# relay_matrix.net
KiCad netlist of a schematic drawn in Altium Designer
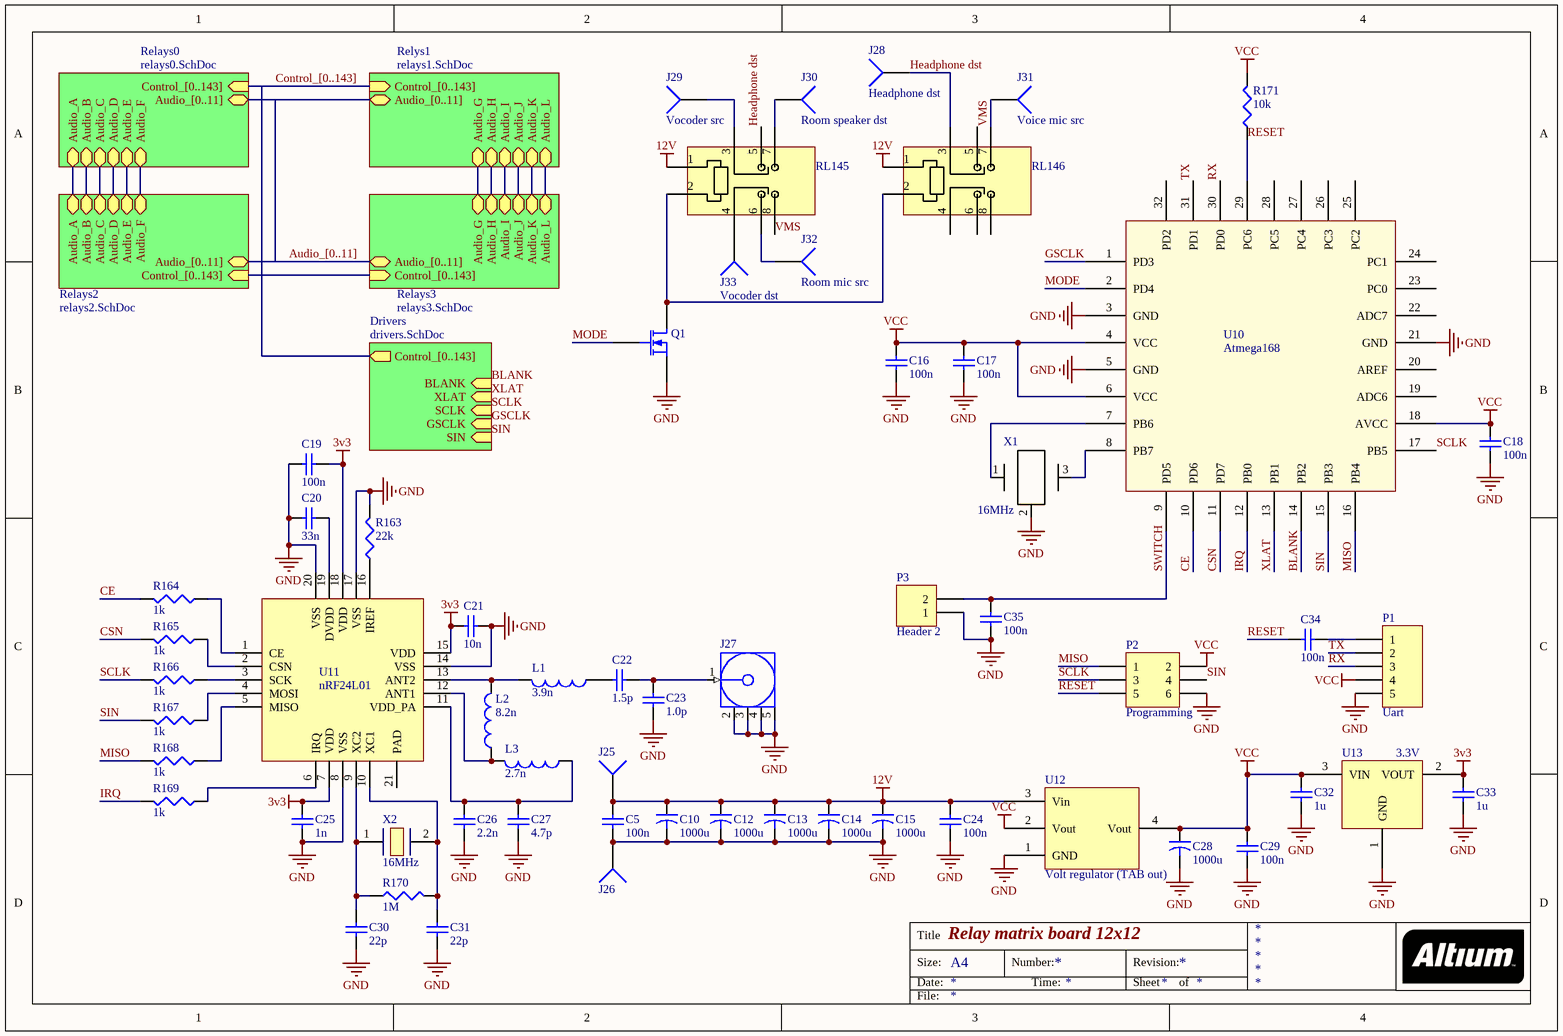
[diagram p0: relay_matrix.SchDoc]

(export (version "E")
  (design (tool "Eeschema 10.0.6"))
  (components
    (comp (ref "C5")
      (value "100n")
      (footprint "1608[0603]")
      (description "Capacitor (Semiconductor SIM Model)")
      (fields (field (name "Comment") "Cap Semi") (field (name "PUBLISHER") "Altium Limited"))
      (libsource (lib "Miscellaneous Devices") (part "Cap Semi"))
    )
    (comp (ref "C10")
      (value "1000u")
      (footprint "Cap_10x16mm")
      (description "Capacitor")
      (fields (field (name "Comment") "Cap2") (field (name "PUBLISHER") "Altium Limited"))
      (libsource (lib "Miscellaneous Devices") (part "Cap2"))
    )
    (comp (ref "C12")
      (value "1000u")
      (footprint "Cap_10x16mm")
      (description "Capacitor")
      (fields (field (name "Comment") "Cap2") (field (name "PUBLISHER") "Altium Limited"))
      (libsource (lib "Miscellaneous Devices") (part "Cap2"))
    )
    (comp (ref "C13")
      (value "1000u")
      (footprint "Cap_10x16mm")
      (description "Capacitor")
      (fields (field (name "Comment") "Cap2") (field (name "PUBLISHER") "Altium Limited"))
      (libsource (lib "Miscellaneous Devices") (part "Cap2"))
    )
    (comp (ref "C14")
      (value "1000u")
      (footprint "Cap_10x16mm")
      (description "Capacitor")
      (fields (field (name "Comment") "Cap2") (field (name "PUBLISHER") "Altium Limited"))
      (libsource (lib "Miscellaneous Devices") (part "Cap2"))
    )
    (comp (ref "C15")
      (value "1000u")
      (footprint "Cap_10x16mm")
      (description "Capacitor")
      (fields (field (name "Comment") "Cap2") (field (name "PUBLISHER") "Altium Limited"))
      (libsource (lib "Miscellaneous Devices") (part "Cap2"))
    )
    (comp (ref "C16")
      (value "100n")
      (footprint "1608[0603]")
      (description "Capacitor (Semiconductor SIM Model)")
      (fields (field (name "Comment") "Cap Semi") (field (name "PUBLISHER") "Altium Limited"))
      (libsource (lib "Miscellaneous Devices") (part "Cap Semi"))
    )
    (comp (ref "C17")
      (value "100n")
      (footprint "1608[0603]")
      (description "Capacitor (Semiconductor SIM Model)")
      (fields (field (name "Comment") "Cap Semi") (field (name "PUBLISHER") "Altium Limited"))
      (libsource (lib "Miscellaneous Devices") (part "Cap Semi"))
    )
    (comp (ref "C18")
      (value "100n")
      (footprint "1608[0603]")
      (description "Capacitor (Semiconductor SIM Model)")
      (fields (field (name "Comment") "Cap Semi") (field (name "PUBLISHER") "Altium Limited"))
      (libsource (lib "Miscellaneous Devices") (part "Cap Semi"))
    )
    (comp (ref "C19")
      (value "100n")
      (footprint "1608[0603]")
      (description "Capacitor (Semiconductor SIM Model)")
      (fields (field (name "Comment") "Cap Semi") (field (name "PUBLISHER") "Altium Limited"))
      (libsource (lib "Miscellaneous Devices") (part "Cap Semi"))
    )
    (comp (ref "C20")
      (value "33n")
      (footprint "1608[0603]")
      (description "Capacitor (Semiconductor SIM Model)")
      (fields (field (name "Comment") "Cap Semi") (field (name "PUBLISHER") "Altium Limited"))
      (libsource (lib "Miscellaneous Devices") (part "Cap Semi"))
    )
    (comp (ref "C21")
      (value "10n")
      (footprint "1608[0603]")
      (description "Capacitor (Semiconductor SIM Model)")
      (fields (field (name "Comment") "Cap Semi") (field (name "PUBLISHER") "Altium Limited"))
      (libsource (lib "Miscellaneous Devices") (part "Cap Semi"))
    )
    (comp (ref "C22")
      (value "1.5p")
      (footprint "1608[0603]")
      (description "Capacitor (Semiconductor SIM Model)")
      (fields (field (name "Comment") "Cap Semi") (field (name "PUBLISHER") "Altium Limited"))
      (libsource (lib "Miscellaneous Devices") (part "Cap Semi"))
    )
    (comp (ref "C23")
      (value "1.0p")
      (footprint "1608[0603]")
      (description "Capacitor (Semiconductor SIM Model)")
      (fields (field (name "Comment") "Cap Semi") (field (name "PUBLISHER") "Altium Limited"))
      (libsource (lib "Miscellaneous Devices") (part "Cap Semi"))
    )
    (comp (ref "C24")
      (value "100n")
      (footprint "1608[0603]")
      (description "Capacitor (Semiconductor SIM Model)")
      (fields (field (name "Comment") "Cap Semi") (field (name "PUBLISHER") "Altium Limited"))
      (libsource (lib "Miscellaneous Devices") (part "Cap Semi"))
    )
    (comp (ref "C25")
      (value "1n")
      (footprint "1608[0603]")
      (description "Capacitor (Semiconductor SIM Model)")
      (fields (field (name "Comment") "Cap Semi") (field (name "PUBLISHER") "Altium Limited"))
      (libsource (lib "Miscellaneous Devices") (part "Cap Semi"))
    )
    (comp (ref "C26")
      (value "2.2n")
      (footprint "1608[0603]")
      (description "Capacitor (Semiconductor SIM Model)")
      (fields (field (name "Comment") "Cap Semi") (field (name "PUBLISHER") "Altium Limited"))
      (libsource (lib "Miscellaneous Devices") (part "Cap Semi"))
    )
    (comp (ref "C27")
      (value "4.7p")
      (footprint "1608[0603]")
      (description "Capacitor (Semiconductor SIM Model)")
      (fields (field (name "Comment") "Cap Semi") (field (name "PUBLISHER") "Altium Limited"))
      (libsource (lib "Miscellaneous Devices") (part "Cap Semi"))
    )
    (comp (ref "C28")
      (value "1000u")
      (footprint "Cap_10x16mm")
      (description "Capacitor")
      (fields (field (name "Comment") "Cap2") (field (name "PUBLISHER") "Altium Limited"))
      (libsource (lib "Miscellaneous Devices") (part "Cap2"))
    )
    (comp (ref "C29")
      (value "100n")
      (footprint "1608[0603]")
      (description "Capacitor (Semiconductor SIM Model)")
      (fields (field (name "Comment") "Cap Semi") (field (name "PUBLISHER") "Altium Limited"))
      (libsource (lib "Miscellaneous Devices") (part "Cap Semi"))
    )
    (comp (ref "C30")
      (value "22p")
      (footprint "1608[0603]")
      (description "Capacitor (Semiconductor SIM Model)")
      (fields (field (name "Comment") "Cap Semi") (field (name "PUBLISHER") "Altium Limited"))
      (libsource (lib "Miscellaneous Devices") (part "Cap Semi"))
    )
    (comp (ref "C31")
      (value "22p")
      (footprint "1608[0603]")
      (description "Capacitor (Semiconductor SIM Model)")
      (fields (field (name "Comment") "Cap Semi") (field (name "PUBLISHER") "Altium Limited"))
      (libsource (lib "Miscellaneous Devices") (part "Cap Semi"))
    )
    (comp (ref "C32")
      (value "1u")
      (footprint "1608[0603]")
      (description "Capacitor (Semiconductor SIM Model)")
      (fields (field (name "Comment") "Cap Semi") (field (name "PUBLISHER") "Altium Limited"))
      (libsource (lib "Miscellaneous Devices") (part "Cap Semi"))
    )
    (comp (ref "C33")
      (value "1u")
      (footprint "1608[0603]")
      (description "Capacitor (Semiconductor SIM Model)")
      (fields (field (name "Comment") "Cap Semi") (field (name "PUBLISHER") "Altium Limited"))
      (libsource (lib "Miscellaneous Devices") (part "Cap Semi"))
    )
    (comp (ref "C34")
      (value "100n")
      (footprint "1608[0603]")
      (description "Capacitor (Semiconductor SIM Model)")
      (fields (field (name "Comment") "Cap Semi") (field (name "PUBLISHER") "Altium Limited"))
      (libsource (lib "Miscellaneous Devices") (part "Cap Semi"))
    )
    (comp (ref "C35")
      (value "100n")
      (footprint "1608[0603]")
      (description "Capacitor (Semiconductor SIM Model)")
      (fields (field (name "Comment") "Cap Semi") (field (name "PUBLISHER") "Altium Limited"))
      (libsource (lib "Miscellaneous Devices") (part "Cap Semi"))
    )
    (comp (ref "J25")
      (value "Audio")
      (footprint "Conn_1_2x4")
      (description "Socket")
      (fields (field (name "PUBLISHER") "Altium Limited"))
      (libsource (lib "Miscellaneous Connectors") (part "Socket"))
    )
    (comp (ref "J26")
      (value "Audio")
      (footprint "Conn_1_2x4")
      (description "Socket")
      (fields (field (name "PUBLISHER") "Altium Limited"))
      (libsource (lib "Miscellaneous Connectors") (part "Socket"))
    )
    (comp (ref "J27")
      (value "COAX-F")
      (footprint "MCX5.08-H5")
      (fields (field (name "PUBLISHER") "Altium Limited"))
      (libsource (lib "Miscellaneous Connectors") (part "COAX-F"))
    )
    (comp (ref "J28")
      (value "Headphone dst")
      (footprint "Conn_1_2x4")
      (description "Socket")
      (fields (field (name "PUBLISHER") "Altium Limited"))
      (libsource (lib "Miscellaneous Connectors") (part "Socket"))
    )
    (comp (ref "J29")
      (value "Vocoder src")
      (footprint "Conn_1_2x4")
      (description "Socket")
      (fields (field (name "PUBLISHER") "Altium Limited"))
      (libsource (lib "Miscellaneous Connectors") (part "Socket"))
    )
    (comp (ref "J30")
      (value "Room speaker dst")
      (footprint "Conn_1_2x4")
      (description "Socket")
      (fields (field (name "PUBLISHER") "Altium Limited"))
      (libsource (lib "Miscellaneous Connectors") (part "Socket"))
    )
    (comp (ref "J31")
      (value "Voice mic src")
      (footprint "Conn_1_2x4")
      (description "Socket")
      (fields (field (name "PUBLISHER") "Altium Limited"))
      (libsource (lib "Miscellaneous Connectors") (part "Socket"))
    )
    (comp (ref "J32")
      (value "Room mic src")
      (footprint "Conn_1_2x4")
      (description "Socket")
      (fields (field (name "PUBLISHER") "Altium Limited"))
      (libsource (lib "Miscellaneous Connectors") (part "Socket"))
    )
    (comp (ref "J33")
      (value "Vocoder dst")
      (footprint "Conn_1_2x4")
      (description "Socket")
      (fields (field (name "PUBLISHER") "Altium Limited"))
      (libsource (lib "Miscellaneous Connectors") (part "Socket"))
    )
    (comp (ref "L1")
      (value "3.9n")
      (footprint "1608[0603]")
      (description "Inductor")
      (fields (field (name "PUBLISHER") "Altium Limited"))
      (libsource (lib "Miscellaneous Devices") (part "Inductor"))
    )
    (comp (ref "L2")
      (value "8.2n")
      (footprint "1608[0603]")
      (description "Inductor")
      (fields (field (name "PUBLISHER") "Altium Limited"))
      (libsource (lib "Miscellaneous Devices") (part "Inductor"))
    )
    (comp (ref "L3")
      (value "2.7n")
      (footprint "1608[0603]")
      (description "Inductor")
      (fields (field (name "PUBLISHER") "Altium Limited"))
      (libsource (lib "Miscellaneous Devices") (part "Inductor"))
    )
    (comp (ref "P1")
      (value "Uart")
      (footprint "HDR1X5")
      (description "Header, 5-Pin")
      (fields (field (name "PUBLISHER") "Altium Limited"))
      (libsource (lib "Miscellaneous Connectors") (part "Header 5"))
    )
    (comp (ref "P2")
      (value "Programming")
      (footprint "HDR2X3H")
      (description "Header, 3-Pin, Dual row, Right Angle")
      (fields (field (name "PUBLISHER") "Altium Limited"))
      (libsource (lib "Miscellaneous Connectors") (part "Header 3X2H"))
    )
    (comp (ref "P3")
      (value "Header 2")
      (footprint "HDR1X2")
      (description "Header, 2-Pin")
      (fields (field (name "PUBLISHER") "Altium Limited"))
      (libsource (lib "Miscellaneous Connectors") (part "Header 2"))
    )
    (comp (ref "Q1")
      (value "MOSFET-N")
      (footprint "SOT23_M")
      (description "N-Channel MOSFET")
      (fields (field (name "PUBLISHER") "Altium Limited"))
      (libsource (lib "Miscellaneous Devices") (part "MOSFET-N"))
    )
    (comp (ref "R163")
      (value "22k")
      (footprint "J1-0603")
      (description "Resistor")
      (fields (field (name "Comment") "Res3") (field (name "PUBLISHER") "Altium Limited"))
      (libsource (lib "Miscellaneous Devices") (part "Res3"))
    )
    (comp (ref "R164")
      (value "1k")
      (footprint "J1-0603")
      (description "Resistor")
      (fields (field (name "Comment") "Res3") (field (name "PUBLISHER") "Altium Limited"))
      (libsource (lib "Miscellaneous Devices") (part "Res3"))
    )
    (comp (ref "R165")
      (value "1k")
      (footprint "J1-0603")
      (description "Resistor")
      (fields (field (name "Comment") "Res3") (field (name "PUBLISHER") "Altium Limited"))
      (libsource (lib "Miscellaneous Devices") (part "Res3"))
    )
    (comp (ref "R166")
      (value "1k")
      (footprint "J1-0603")
      (description "Resistor")
      (fields (field (name "Comment") "Res3") (field (name "PUBLISHER") "Altium Limited"))
      (libsource (lib "Miscellaneous Devices") (part "Res3"))
    )
    (comp (ref "R167")
      (value "1k")
      (footprint "J1-0603")
      (description "Resistor")
      (fields (field (name "Comment") "Res3") (field (name "PUBLISHER") "Altium Limited"))
      (libsource (lib "Miscellaneous Devices") (part "Res3"))
    )
    (comp (ref "R168")
      (value "1k")
      (footprint "J1-0603")
      (description "Resistor")
      (fields (field (name "Comment") "Res3") (field (name "PUBLISHER") "Altium Limited"))
      (libsource (lib "Miscellaneous Devices") (part "Res3"))
    )
    (comp (ref "R169")
      (value "1k")
      (footprint "J1-0603")
      (description "Resistor")
      (fields (field (name "Comment") "Res3") (field (name "PUBLISHER") "Altium Limited"))
      (libsource (lib "Miscellaneous Devices") (part "Res3"))
    )
    (comp (ref "R170")
      (value "1M")
      (footprint "J1-0603")
      (description "Resistor")
      (fields (field (name "Comment") "Res3") (field (name "PUBLISHER") "Altium Limited"))
      (libsource (lib "Miscellaneous Devices") (part "Res3"))
    )
    (comp (ref "R171")
      (value "10k")
      (footprint "J1-0603")
      (description "Resistor")
      (fields (field (name "Comment") "Res3") (field (name "PUBLISHER") "Altium Limited"))
      (libsource (lib "Miscellaneous Devices") (part "Res3"))
    )
    (comp (ref "RL145")
      (value "Relay")
      (footprint "Relay_S13")
      (description "Miniature power relay")
      (fields (field (name "PART NUMBER") "S13-12V-2C"))
      (libsource (lib "tech-thing") (part "Relay_S13"))
    )
    (comp (ref "RL146")
      (value "Relay")
      (footprint "Relay_S13")
      (description "Miniature power relay")
      (fields (field (name "PART NUMBER") "S13-12V-2C"))
      (libsource (lib "tech-thing") (part "Relay_S13"))
    )
    (comp (ref "U10")
      (value "Atmega168")
      (footprint "TQFP-32")
      (libsource (lib "tech-thing") (part "Atmega168"))
    )
    (comp (ref "U11")
      (value "nRF24L01")
      (footprint "QFN20")
      (description "Single Chip 2.4GHz Transciever")
      (libsource (lib "tech-thing") (part "nRF24L01"))
    )
    (comp (ref "U12")
      (value "Volt regulator (TAB out)")
      (footprint "SOT223")
      (description "AP1117")
      (fields (field (name "PART NUMBER") "1825292"))
      (libsource (lib "tech-thing") (part "Volt regulator (TAB out)"))
    )
    (comp (ref "U13")
      (value "3.3V")
      (footprint "SOT23")
      (description "Fixed voltage regulator")
      (fields (field (name "PART NUMBER") "2363085"))
      (libsource (lib "tech-thing") (part "Voltage_regulator_3pin"))
    )
    (comp (ref "X1")
      (value "16MHz")
      (footprint "SMD-RESONATOR")
      (fields (field (name "Comment") "Resonator"))
      (libsource (lib "tech-thing") (part "Resonator"))
    )
    (comp (ref "X2")
      (value "16MHz")
      (footprint "Crystal_7A_series")
      (fields (field (name "Comment") "Crystal"))
      (libsource (lib "tech-thing") (part "Crystal"))
    )
  )
  (nets
    (net (code "171") (name "/BLANK") (class "Default")
      (node (ref "U10") (pin "14") (pinfunction "PB2_14") (pintype "passive"))
    )
    (net (code "172") (name "/CE") (class "Default")
      (node (ref "R164") (pin "2") (pinfunction "2_2") (pintype "passive"))
      (node (ref "U10") (pin "10") (pinfunction "PD6_10") (pintype "passive"))
    )
    (net (code "173") (name "/CSN") (class "Default")
      (node (ref "R165") (pin "2") (pinfunction "2_2") (pintype "passive"))
      (node (ref "U10") (pin "11") (pinfunction "PD7_11") (pintype "passive"))
    )
    (net (code "177") (name "/GSCLK") (class "Default")
      (node (ref "U10") (pin "1") (pinfunction "PD3_1") (pintype "passive"))
    )
    (net (code "178") (name "/Headphone dst") (class "Default")
      (node (ref "J28") (pin "1") (pinfunction "1_1") (pintype "passive"))
      (node (ref "RL145") (pin "5") (pintype "passive"))
      (node (ref "RL146") (pin "3") (pintype "passive"))
    )
    (net (code "179") (name "/IRQ") (class "Default")
      (node (ref "R169") (pin "2") (pinfunction "2_2") (pintype "passive"))
      (node (ref "U10") (pin "12") (pinfunction "PB0_12") (pintype "passive"))
    )
    (net (code "180") (name "/MISO") (class "Default")
      (node (ref "P2") (pin "1") (pinfunction "1_1") (pintype "passive"))
      (node (ref "R168") (pin "2") (pinfunction "2_2") (pintype "passive"))
      (node (ref "U10") (pin "16") (pinfunction "PB4_16") (pintype "passive"))
    )
    (net (code "181") (name "/MODE") (class "Default")
      (node (ref "Q1") (pin "2") (pinfunction "G_2") (pintype "passive"))
      (node (ref "U10") (pin "2") (pinfunction "PD4_2") (pintype "passive"))
    )
    (net (code "182") (name "/RESET") (class "Default")
      (node (ref "C34") (pin "1") (pinfunction "1_1") (pintype "passive"))
      (node (ref "P2") (pin "5") (pinfunction "5_5") (pintype "passive"))
      (node (ref "R171") (pin "1") (pinfunction "1_1") (pintype "passive"))
      (node (ref "U10") (pin "29") (pinfunction "PC6_29") (pintype "passive"))
    )
    (net (code "183") (name "/RX") (class "Default")
      (node (ref "P1") (pin "3") (pinfunction "3_3") (pintype "passive"))
      (node (ref "U10") (pin "30") (pinfunction "PD0_30") (pintype "passive"))
    )
    (net (code "184") (name "/SCLK") (class "Default")
      (node (ref "P2") (pin "3") (pinfunction "3_3") (pintype "passive"))
      (node (ref "R166") (pin "2") (pinfunction "2_2") (pintype "passive"))
      (node (ref "U10") (pin "17") (pinfunction "PB5_17") (pintype "passive"))
    )
    (net (code "185") (name "/SIN") (class "Default")
      (node (ref "P2") (pin "4") (pinfunction "4_4") (pintype "passive"))
      (node (ref "R167") (pin "2") (pinfunction "2_2") (pintype "passive"))
      (node (ref "U10") (pin "15") (pinfunction "PB3_15") (pintype "passive"))
    )
    (net (code "186") (name "/SWITCH") (class "Default")
      (node (ref "C35") (pin "1") (pinfunction "1_1") (pintype "passive"))
      (node (ref "P3") (pin "2") (pinfunction "2_2") (pintype "passive"))
      (node (ref "U10") (pin "9") (pinfunction "PD5_9") (pintype "passive"))
    )
    (net (code "187") (name "/TX") (class "Default")
      (node (ref "P1") (pin "2") (pinfunction "2_2") (pintype "passive"))
      (node (ref "U10") (pin "31") (pinfunction "PD1_31") (pintype "passive"))
    )
    (net (code "188") (name "/VMS") (class "Default")
      (node (ref "J31") (pin "1") (pinfunction "1_1") (pintype "passive"))
      (node (ref "RL145") (pin "8") (pinfunction "8_8") (pintype "passive"))
      (node (ref "RL146") (pin "7") (pintype "passive"))
    )
    (net (code "189") (name "/XLAT") (class "Default")
      (node (ref "U10") (pin "13") (pinfunction "PB1_13") (pintype "passive"))
    )
    (net (code "190") (name "3v3") (class "Default")
      (node (ref "C19") (pin "2") (pinfunction "2_2") (pintype "passive"))
      (node (ref "C21") (pin "1") (pinfunction "1_1") (pintype "passive"))
      (node (ref "C25") (pin "1") (pinfunction "1_1") (pintype "passive"))
      (node (ref "C33") (pin "1") (pinfunction "1_1") (pintype "passive"))
      (node (ref "U11") (pin "15") (pinfunction "VDD_15") (pintype "passive"))
      (node (ref "U11") (pin "18") (pinfunction "VDD_18") (pintype "passive"))
      (node (ref "U11") (pin "7") (pinfunction "VDD_7") (pintype "passive"))
      (node (ref "U13") (pin "2") (pinfunction "VOUT_2") (pintype "passive"))
    )
    (net (code "191") (name "12V") (class "Default")
      (node (ref "C10") (pin "1") (pinfunction "1_1") (pintype "passive"))
      (node (ref "C12") (pin "1") (pinfunction "1_1") (pintype "passive"))
      (node (ref "C13") (pin "1") (pinfunction "1_1") (pintype "passive"))
      (node (ref "C14") (pin "1") (pinfunction "1_1") (pintype "passive"))
      (node (ref "C15") (pin "1") (pinfunction "1_1") (pintype "passive"))
      (node (ref "C24") (pin "1") (pinfunction "1_1") (pintype "passive"))
      (node (ref "C5") (pin "1") (pinfunction "1_1") (pintype "passive"))
      (node (ref "J25") (pin "1") (pinfunction "1_1") (pintype "passive"))
      (node (ref "RL145") (pin "1") (pintype "passive"))
      (node (ref "RL146") (pin "1") (pintype "passive"))
      (node (ref "U12") (pin "3") (pinfunction "Vin_3") (pintype "passive"))
    )
    (net (code "192") (name "GND") (class "Default")
      (node (ref "C10") (pin "2") (pinfunction "2_2") (pintype "passive"))
      (node (ref "C12") (pin "2") (pinfunction "2_2") (pintype "passive"))
      (node (ref "C13") (pin "2") (pinfunction "2_2") (pintype "passive"))
      (node (ref "C14") (pin "2") (pinfunction "2_2") (pintype "passive"))
      (node (ref "C15") (pin "2") (pinfunction "2_2") (pintype "passive"))
      (node (ref "C16") (pin "2") (pinfunction "2_2") (pintype "passive"))
      (node (ref "C17") (pin "2") (pinfunction "2_2") (pintype "passive"))
      (node (ref "C18") (pin "2") (pinfunction "2_2") (pintype "passive"))
      (node (ref "C19") (pin "1") (pinfunction "1_1") (pintype "passive"))
      (node (ref "C20") (pin "1") (pinfunction "1_1") (pintype "passive"))
      (node (ref "C21") (pin "2") (pinfunction "2_2") (pintype "passive"))
      (node (ref "C23") (pin "2") (pinfunction "2_2") (pintype "passive"))
      (node (ref "C24") (pin "2") (pinfunction "2_2") (pintype "passive"))
      (node (ref "C25") (pin "2") (pinfunction "2_2") (pintype "passive"))
      (node (ref "C26") (pin "2") (pinfunction "2_2") (pintype "passive"))
      (node (ref "C27") (pin "2") (pinfunction "2_2") (pintype "passive"))
      (node (ref "C28") (pin "2") (pinfunction "2_2") (pintype "passive"))
      (node (ref "C29") (pin "2") (pinfunction "2_2") (pintype "passive"))
      (node (ref "C30") (pin "2") (pinfunction "2_2") (pintype "passive"))
      (node (ref "C31") (pin "2") (pinfunction "2_2") (pintype "passive"))
      (node (ref "C32") (pin "2") (pinfunction "2_2") (pintype "passive"))
      (node (ref "C33") (pin "2") (pinfunction "2_2") (pintype "passive"))
      (node (ref "C35") (pin "2") (pinfunction "2_2") (pintype "passive"))
      (node (ref "C5") (pin "2") (pinfunction "2_2") (pintype "passive"))
      (node (ref "J26") (pin "1") (pinfunction "1_1") (pintype "passive"))
      (node (ref "J27") (pin "2") (pinfunction "GND_2") (pintype "power_in"))
      (node (ref "J27") (pin "3") (pinfunction "GND_3") (pintype "power_in"))
      (node (ref "J27") (pin "4") (pinfunction "GND_4") (pintype "power_in"))
      (node (ref "J27") (pin "5") (pinfunction "GND_5") (pintype "power_in"))
      (node (ref "P1") (pin "5") (pinfunction "5_5") (pintype "passive"))
      (node (ref "P2") (pin "6") (pinfunction "6_6") (pintype "passive"))
      (node (ref "P3") (pin "1") (pinfunction "1_1") (pintype "passive"))
      (node (ref "Q1") (pin "3") (pinfunction "S_3") (pintype "passive"))
      (node (ref "R163") (pin "2") (pinfunction "2_2") (pintype "passive"))
      (node (ref "U10") (pin "21") (pinfunction "GND_21") (pintype "passive"))
      (node (ref "U10") (pin "3") (pinfunction "GND_3") (pintype "passive"))
      (node (ref "U10") (pin "5") (pinfunction "GND_5") (pintype "passive"))
      (node (ref "U11") (pin "14") (pinfunction "VSS_14") (pintype "passive"))
      (node (ref "U11") (pin "17") (pinfunction "VSS_17") (pintype "passive"))
      (node (ref "U11") (pin "20") (pinfunction "VSS_20") (pintype "passive"))
      (node (ref "U11") (pin "8") (pinfunction "VSS_8") (pintype "passive"))
      (node (ref "U12") (pin "1") (pinfunction "GND_1") (pintype "passive"))
      (node (ref "U13") (pin "1") (pinfunction "GND_1") (pintype "passive"))
      (node (ref "X1") (pin "2") (pinfunction "12_2") (pintype "passive"))
    )
    (net (code "193") (name "Net-(C22-Pad1)") (class "Default")
      (node (ref "C22") (pin "1") (pinfunction "1_1") (pintype "passive"))
      (node (ref "L1") (pin "1") (pinfunction "1_1") (pintype "passive"))
    )
    (net (code "194") (name "Net-(C34-Pad2)") (class "Default")
      (node (ref "C34") (pin "2") (pinfunction "2_2") (pintype "passive"))
      (node (ref "P1") (pin "1") (pinfunction "1_1") (pintype "passive"))
    )
    (net (code "195") (name "Net-(J27-Signal)") (class "Default")
      (node (ref "C22") (pin "2") (pinfunction "2_2") (pintype "passive"))
      (node (ref "C23") (pin "1") (pinfunction "1_1") (pintype "passive"))
      (node (ref "J27") (pin "1") (pinfunction "Signal_1") (pintype "input"))
    )
    (net (code "196") (name "Net-(J29-Pad1)") (class "Default")
      (node (ref "J29") (pin "1") (pinfunction "1_1") (pintype "passive"))
      (node (ref "RL145") (pin "3") (pintype "passive"))
    )
    (net (code "197") (name "Net-(J30-Pad1)") (class "Default")
      (node (ref "J30") (pin "1") (pinfunction "1_1") (pintype "passive"))
      (node (ref "RL145") (pin "7") (pintype "passive"))
    )
    (net (code "198") (name "Net-(J32-Pad1)") (class "Default")
      (node (ref "J32") (pin "1") (pinfunction "1_1") (pintype "passive"))
      (node (ref "RL145") (pin "6") (pintype "passive"))
    )
    (net (code "199") (name "Net-(J33-Pad1)") (class "Default")
      (node (ref "J33") (pin "1") (pinfunction "1_1") (pintype "passive"))
      (node (ref "RL145") (pin "4") (pintype "passive"))
    )
    (net (code "200") (name "Net-(Q1-D)") (class "Default")
      (node (ref "Q1") (pin "1") (pinfunction "D_1") (pintype "passive"))
      (node (ref "RL145") (pin "2") (pintype "passive"))
      (node (ref "RL146") (pin "2") (pintype "passive"))
    )
    (net (code "201") (name "Net-(U10-PB6)") (class "Default")
      (node (ref "U10") (pin "7") (pinfunction "PB6_7") (pintype "passive"))
      (node (ref "X1") (pin "1") (pinfunction "11_1") (pintype "passive"))
    )
    (net (code "202") (name "Net-(U10-PB7)") (class "Default")
      (node (ref "U10") (pin "8") (pinfunction "PB7_8") (pintype "passive"))
      (node (ref "X1") (pin "3") (pinfunction "13_3") (pintype "passive"))
    )
    (net (code "203") (name "Net-(U11-ANT1)") (class "Default")
      (node (ref "L2") (pin "1") (pinfunction "1_1") (pintype "passive"))
      (node (ref "L3") (pin "2") (pinfunction "2_2") (pintype "passive"))
      (node (ref "U11") (pin "12") (pinfunction "ANT1_12") (pintype "passive"))
    )
    (net (code "204") (name "Net-(U11-ANT2)") (class "Default")
      (node (ref "L1") (pin "2") (pinfunction "2_2") (pintype "passive"))
      (node (ref "L2") (pin "2") (pinfunction "2_2") (pintype "passive"))
      (node (ref "U11") (pin "13") (pinfunction "ANT2_13") (pintype "passive"))
    )
    (net (code "205") (name "Net-(U11-CE)") (class "Default")
      (node (ref "R164") (pin "1") (pinfunction "1_1") (pintype "passive"))
      (node (ref "U11") (pin "1") (pinfunction "CE_1") (pintype "passive"))
    )
    (net (code "206") (name "Net-(U11-CSN)") (class "Default")
      (node (ref "R165") (pin "1") (pinfunction "1_1") (pintype "passive"))
      (node (ref "U11") (pin "2") (pinfunction "CSN_2") (pintype "passive"))
    )
    (net (code "207") (name "Net-(U11-DVDD)") (class "Default")
      (node (ref "C20") (pin "2") (pinfunction "2_2") (pintype "passive"))
      (node (ref "U11") (pin "19") (pinfunction "DVDD_19") (pintype "passive"))
    )
    (net (code "208") (name "Net-(U11-IREF)") (class "Default")
      (node (ref "R163") (pin "1") (pinfunction "1_1") (pintype "passive"))
      (node (ref "U11") (pin "16") (pinfunction "IREF_16") (pintype "passive"))
    )
    (net (code "209") (name "Net-(U11-IRQ)") (class "Default")
      (node (ref "R169") (pin "1") (pinfunction "1_1") (pintype "passive"))
      (node (ref "U11") (pin "6") (pinfunction "IRQ_6") (pintype "passive"))
    )
    (net (code "210") (name "Net-(U11-MISO)") (class "Default")
      (node (ref "R168") (pin "1") (pinfunction "1_1") (pintype "passive"))
      (node (ref "U11") (pin "5") (pinfunction "MISO_5") (pintype "passive"))
    )
    (net (code "211") (name "Net-(U11-MOSI)") (class "Default")
      (node (ref "R167") (pin "1") (pinfunction "1_1") (pintype "passive"))
      (node (ref "U11") (pin "4") (pinfunction "MOSI_4") (pintype "passive"))
    )
    (net (code "212") (name "Net-(U11-SCK)") (class "Default")
      (node (ref "R166") (pin "1") (pinfunction "1_1") (pintype "passive"))
      (node (ref "U11") (pin "3") (pinfunction "SCK_3") (pintype "passive"))
    )
    (net (code "213") (name "Net-(U11-VDD_PA)") (class "Default")
      (node (ref "C26") (pin "1") (pinfunction "1_1") (pintype "passive"))
      (node (ref "C27") (pin "1") (pinfunction "1_1") (pintype "passive"))
      (node (ref "L3") (pin "1") (pinfunction "1_1") (pintype "passive"))
      (node (ref "U11") (pin "11") (pinfunction "VDD_PA_11") (pintype "passive"))
    )
    (net (code "214") (name "Net-(U11-XC1)") (class "Default")
      (node (ref "C31") (pin "1") (pinfunction "1_1") (pintype "passive"))
      (node (ref "R170") (pin "2") (pinfunction "2_2") (pintype "passive"))
      (node (ref "U11") (pin "10") (pinfunction "XC1_10") (pintype "passive"))
      (node (ref "X2") (pin "2") (pintype "passive"))
    )
    (net (code "215") (name "Net-(U11-XC2)") (class "Default")
      (node (ref "C30") (pin "1") (pinfunction "1_1") (pintype "passive"))
      (node (ref "R170") (pin "1") (pinfunction "1_1") (pintype "passive"))
      (node (ref "U11") (pin "9") (pinfunction "XC2_9") (pintype "passive"))
      (node (ref "X2") (pin "1") (pintype "passive"))
    )
    (net (code "216") (name "VCC") (class "Default")
      (node (ref "C16") (pin "1") (pinfunction "1_1") (pintype "passive"))
      (node (ref "C17") (pin "1") (pinfunction "1_1") (pintype "passive"))
      (node (ref "C18") (pin "1") (pinfunction "1_1") (pintype "passive"))
      (node (ref "C28") (pin "1") (pinfunction "1_1") (pintype "passive"))
      (node (ref "C29") (pin "1") (pinfunction "1_1") (pintype "passive"))
      (node (ref "C32") (pin "1") (pinfunction "1_1") (pintype "passive"))
      (node (ref "P1") (pin "4") (pinfunction "4_4") (pintype "passive"))
      (node (ref "P2") (pin "2") (pinfunction "2_2") (pintype "passive"))
      (node (ref "R171") (pin "2") (pinfunction "2_2") (pintype "passive"))
      (node (ref "U10") (pin "18") (pinfunction "AVCC_18") (pintype "passive"))
      (node (ref "U10") (pin "4") (pinfunction "VCC_4") (pintype "passive"))
      (node (ref "U10") (pin "6") (pinfunction "VCC_6") (pintype "passive"))
      (node (ref "U12") (pin "2") (pinfunction "Vout_2") (pintype "passive"))
      (node (ref "U12") (pin "4") (pinfunction "Vout_4") (pintype "passive"))
      (node (ref "U13") (pin "3") (pinfunction "VIN_3") (pintype "passive"))
    )
    (net (code "217") (name "unconnected-(RL146-Pad4)") (class "Default")
      (node (ref "RL146") (pin "4") (pintype "passive"))
    )
    (net (code "218") (name "unconnected-(RL146-Pad5)") (class "Default")
      (node (ref "RL146") (pin "5") (pintype "passive"))
    )
    (net (code "219") (name "unconnected-(RL146-Pad6)") (class "Default")
      (node (ref "RL146") (pin "6") (pintype "passive"))
    )
    (net (code "220") (name "unconnected-(RL146-Pad8)") (class "Default")
      (node (ref "RL146") (pin "8") (pinfunction "8_8") (pintype "passive"))
    )
    (net (code "221") (name "unconnected-(U10-ADC6-Pad19)") (class "Default")
      (node (ref "U10") (pin "19") (pinfunction "ADC6_19") (pintype "passive"))
    )
    (net (code "222") (name "unconnected-(U10-ADC7-Pad22)") (class "Default")
      (node (ref "U10") (pin "22") (pinfunction "ADC7_22") (pintype "passive"))
    )
    (net (code "223") (name "unconnected-(U10-AREF-Pad20)") (class "Default")
      (node (ref "U10") (pin "20") (pinfunction "AREF_20") (pintype "passive"))
    )
    (net (code "224") (name "unconnected-(U10-PC0-Pad23)") (class "Default")
      (node (ref "U10") (pin "23") (pinfunction "PC0_23") (pintype "passive"))
    )
    (net (code "225") (name "unconnected-(U10-PC1-Pad24)") (class "Default")
      (node (ref "U10") (pin "24") (pinfunction "PC1_24") (pintype "passive"))
    )
    (net (code "226") (name "unconnected-(U10-PC2-Pad25)") (class "Default")
      (node (ref "U10") (pin "25") (pinfunction "PC2_25") (pintype "passive"))
    )
    (net (code "227") (name "unconnected-(U10-PC3-Pad26)") (class "Default")
      (node (ref "U10") (pin "26") (pinfunction "PC3_26") (pintype "passive"))
    )
    (net (code "228") (name "unconnected-(U10-PC4-Pad27)") (class "Default")
      (node (ref "U10") (pin "27") (pinfunction "PC4_27") (pintype "passive"))
    )
    (net (code "229") (name "unconnected-(U10-PC5-Pad28)") (class "Default")
      (node (ref "U10") (pin "28") (pinfunction "PC5_28") (pintype "passive"))
    )
    (net (code "230") (name "unconnected-(U10-PD2-Pad32)") (class "Default")
      (node (ref "U10") (pin "32") (pinfunction "PD2_32") (pintype "passive"))
    )
    (net (code "231") (name "unconnected-(U11-PAD-Pad21)") (class "Default")
      (node (ref "U11") (pin "21") (pinfunction "PAD_21") (pintype "passive"))
    )
  )
)
